# pay-optical-toplevel.net
KiCad netlist of a schematic drawn in Altium Designer
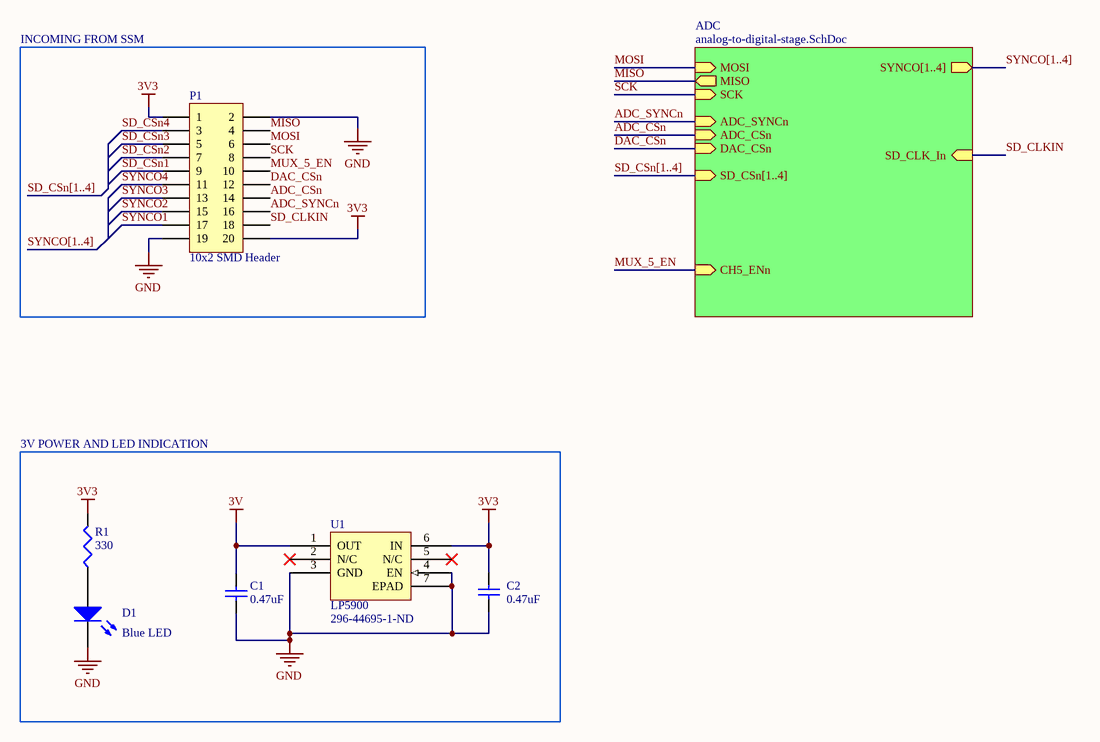
[diagram p0: pay-optical-toplevel.SchDoc]

(export (version "E")
  (design (tool "Eeschema 10.0.6"))
  (components
    (comp (ref "C1")
      (value "0.47uF")
      (footprint "1608[0603]")
      (description "Capacitor (Semiconductor SIM Model)")
      (fields (field (name "PUBLISHER") "Altium Limited"))
      (libsource (lib "Miscellaneous Devices") (part "Cap Semi"))
    )
    (comp (ref "C2")
      (value "0.47uF")
      (footprint "1608[0603]")
      (description "Capacitor (Semiconductor SIM Model)")
      (fields (field (name "PUBLISHER") "Altium Limited"))
      (libsource (lib "Miscellaneous Devices") (part "Cap Semi"))
    )
    (comp (ref "D1")
      (value "Blue LED")
      (footprint "0603-LED")
      (description "Typical RED, GREEN, YELLOW, AMBER GaAs LED")
      (fields (field (name "PUBLISHER") "Altium Limited"))
      (libsource (lib "Miscellaneous Devices") (part "LED2"))
    )
    (comp (ref "P1")
      (value "10x2 SMD Header")
      (footprint "CON20_2X10_DUA00")
      (description "10x2 SMD 50mil Incoming from SSM")
      (fields (field (name "PUBLISHER") "Altium Limited"))
      (libsource (lib "Miscellaneous Connectors") (part "Header 10X2"))
    )
    (comp (ref "R1")
      (value "330")
      (footprint "0402")
      (description "Power indication LED")
      (fields (field (name "PUBLISHER") "Altium Limited"))
      (libsource (lib "Miscellaneous Devices") (part "Res3"))
    )
    (comp (ref "U1")
      (value "LP5900")
      (footprint "DFN220X250X80-7N")
      (description "Low noise 3V low dropout regulator for analog and RF applications.")
      (fields (field (name "SUPPLIER PART NUMBER 1") "296-44695-1-ND"))
      (libsource (lib "PAY") (part "LP5900"))
    )
  )
  (nets
    (net (code "1") (name "/ADC_CSn") (class "Default")
      (node (ref "P1") (pin "14") (pinfunction "14_14") (pintype "passive"))
    )
    (net (code "2") (name "/ADC_SYNCn") (class "Default")
      (node (ref "P1") (pin "16") (pinfunction "16_16") (pintype "passive"))
    )
    (net (code "3") (name "/DAC_CSn") (class "Default")
      (node (ref "P1") (pin "12") (pinfunction "12_12") (pintype "passive"))
    )
    (net (code "4") (name "/MISO") (class "Default")
      (node (ref "P1") (pin "4") (pinfunction "4_4") (pintype "passive"))
    )
    (net (code "5") (name "/MOSI") (class "Default")
      (node (ref "P1") (pin "6") (pinfunction "6_6") (pintype "passive"))
    )
    (net (code "6") (name "/MUX_5_EN") (class "Default")
      (node (ref "P1") (pin "10") (pinfunction "10_10") (pintype "passive"))
    )
    (net (code "7") (name "/SCK") (class "Default")
      (node (ref "P1") (pin "8") (pinfunction "8_8") (pintype "passive"))
    )
    (net (code "8") (name "/SD_CLKIN") (class "Default")
      (node (ref "P1") (pin "18") (pinfunction "18_18") (pintype "passive"))
    )
    (net (code "9") (name "/SD_CSn1") (class "Default")
      (node (ref "P1") (pin "9") (pinfunction "9_9") (pintype "passive"))
    )
    (net (code "10") (name "/SD_CSn2") (class "Default")
      (node (ref "P1") (pin "7") (pinfunction "7_7") (pintype "passive"))
    )
    (net (code "11") (name "/SD_CSn3") (class "Default")
      (node (ref "P1") (pin "5") (pinfunction "5_5") (pintype "passive"))
    )
    (net (code "12") (name "/SD_CSn4") (class "Default")
      (node (ref "P1") (pin "3") (pinfunction "3_3") (pintype "passive"))
    )
    (net (code "14") (name "/SYNCO1") (class "Default")
      (node (ref "P1") (pin "17") (pinfunction "17_17") (pintype "passive"))
    )
    (net (code "15") (name "/SYNCO2") (class "Default")
      (node (ref "P1") (pin "15") (pinfunction "15_15") (pintype "passive"))
    )
    (net (code "16") (name "/SYNCO3") (class "Default")
      (node (ref "P1") (pin "13") (pinfunction "13_13") (pintype "passive"))
    )
    (net (code "17") (name "/SYNCO4") (class "Default")
      (node (ref "P1") (pin "11") (pinfunction "11_11") (pintype "passive"))
    )
    (net (code "19") (name "3V") (class "Default")
      (node (ref "C1") (pin "2") (pinfunction "2_2") (pintype "passive"))
      (node (ref "U1") (pin "1") (pinfunction "OUT_1") (pintype "power_in"))
    )
    (net (code "20") (name "3V3") (class "Default")
      (node (ref "C2") (pin "2") (pinfunction "2_2") (pintype "passive"))
      (node (ref "P1") (pin "1") (pinfunction "1_1") (pintype "passive"))
      (node (ref "P1") (pin "20") (pinfunction "20_20") (pintype "passive"))
      (node (ref "R1") (pin "2") (pinfunction "2_2") (pintype "passive"))
      (node (ref "U1") (pin "6") (pinfunction "IN_6") (pintype "power_in"))
    )
    (net (code "21") (name "GND") (class "Default")
      (node (ref "C1") (pin "1") (pinfunction "1_1") (pintype "passive"))
      (node (ref "C2") (pin "1") (pinfunction "1_1") (pintype "passive"))
      (node (ref "D1") (pin "2") (pinfunction "K_2") (pintype "passive"))
      (node (ref "P1") (pin "19") (pinfunction "19_19") (pintype "passive"))
      (node (ref "P1") (pin "2") (pinfunction "2_2") (pintype "passive"))
      (node (ref "U1") (pin "3") (pinfunction "GND_3") (pintype "power_in"))
      (node (ref "U1") (pin "4") (pinfunction "EN_4") (pintype "input"))
      (node (ref "U1") (pin "7") (pinfunction "EPAD_7") (pintype "passive"))
    )
    (net (code "22") (name "Net-(D1-A)") (class "Default")
      (node (ref "D1") (pin "1") (pinfunction "A_1") (pintype "passive"))
      (node (ref "R1") (pin "1") (pinfunction "1_1") (pintype "passive"))
    )
    (net (code "23") (name "unconnected-(U1-N{slash}C-Pad2)") (class "Default")
      (node (ref "U1") (pin "2") (pinfunction "N/C_2") (pintype "passive+no_connect"))
    )
    (net (code "24") (name "unconnected-(U1-N{slash}C-Pad5)") (class "Default")
      (node (ref "U1") (pin "5") (pinfunction "N/C_5") (pintype "passive+no_connect"))
    )
  )
)
